# switch_2.net
KiCad netlist of a schematic drawn in Altium Designer
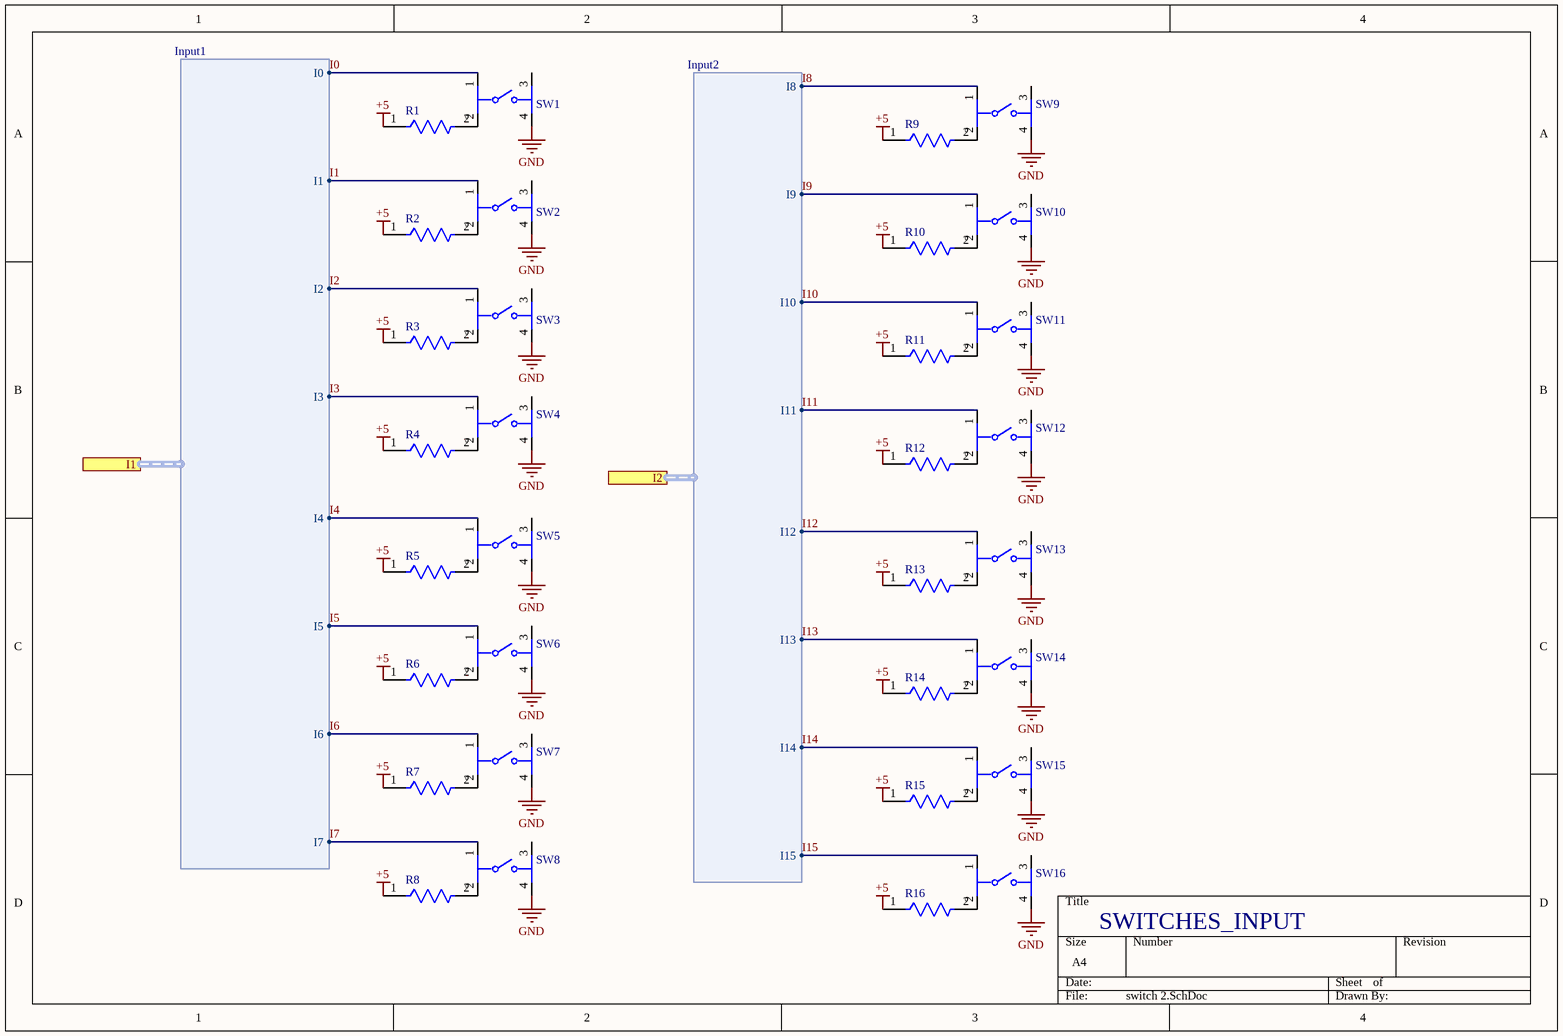
[diagram p0: switch 2.SchDoc]

(export (version "E")
  (design (tool "Eeschema 10.0.6"))
  (components
    (comp (ref "R1")
      (value "MRS25000C1001FCT00")
      (footprint "FP-MRS25-MFG")
      (description "RES 1K OHM 0.6W 1% AXIAL")
      (fields (field (name "TOLERANCE") "1%"))
      (libsource (lib "Altium Content Vault") (part "1029c3af85768c4190bb7ad29bc67b5"))
    )
    (comp (ref "R2")
      (value "MRS25000C1001FCT00")
      (footprint "FP-MRS25-MFG")
      (description "RES 1K OHM 0.6W 1% AXIAL")
      (fields (field (name "TOLERANCE") "1%"))
      (libsource (lib "Altium Content Vault") (part "1029c3af85768c4190bb7ad29bc67b5"))
    )
    (comp (ref "R3")
      (value "MRS25000C1001FCT00")
      (footprint "FP-MRS25-MFG")
      (description "RES 1K OHM 0.6W 1% AXIAL")
      (fields (field (name "TOLERANCE") "1%"))
      (libsource (lib "Altium Content Vault") (part "1029c3af85768c4190bb7ad29bc67b5"))
    )
    (comp (ref "R4")
      (value "MRS25000C1001FCT00")
      (footprint "FP-MRS25-MFG")
      (description "RES 1K OHM 0.6W 1% AXIAL")
      (fields (field (name "TOLERANCE") "1%"))
      (libsource (lib "Altium Content Vault") (part "1029c3af85768c4190bb7ad29bc67b5"))
    )
    (comp (ref "R5")
      (value "MRS25000C1001FCT00")
      (footprint "FP-MRS25-MFG")
      (description "RES 1K OHM 0.6W 1% AXIAL")
      (fields (field (name "TOLERANCE") "1%"))
      (libsource (lib "Altium Content Vault") (part "1029c3af85768c4190bb7ad29bc67b5"))
    )
    (comp (ref "R6")
      (value "MRS25000C1001FCT00")
      (footprint "FP-MRS25-MFG")
      (description "RES 1K OHM 0.6W 1% AXIAL")
      (fields (field (name "TOLERANCE") "1%"))
      (libsource (lib "Altium Content Vault") (part "1029c3af85768c4190bb7ad29bc67b5"))
    )
    (comp (ref "R7")
      (value "MRS25000C1001FCT00")
      (footprint "FP-MRS25-MFG")
      (description "RES 1K OHM 0.6W 1% AXIAL")
      (fields (field (name "TOLERANCE") "1%"))
      (libsource (lib "Altium Content Vault") (part "1029c3af85768c4190bb7ad29bc67b5"))
    )
    (comp (ref "R8")
      (value "MRS25000C1001FCT00")
      (footprint "FP-MRS25-MFG")
      (description "RES 1K OHM 0.6W 1% AXIAL")
      (fields (field (name "TOLERANCE") "1%"))
      (libsource (lib "Altium Content Vault") (part "1029c3af85768c4190bb7ad29bc67b5"))
    )
    (comp (ref "R9")
      (value "MRS25000C1001FCT00")
      (footprint "FP-MRS25-MFG")
      (description "RES 1K OHM 0.6W 1% AXIAL")
      (fields (field (name "TOLERANCE") "1%"))
      (libsource (lib "Altium Content Vault") (part "1029c3af85768c4190bb7ad29bc67b5"))
    )
    (comp (ref "R10")
      (value "MRS25000C1001FCT00")
      (footprint "FP-MRS25-MFG")
      (description "RES 1K OHM 0.6W 1% AXIAL")
      (fields (field (name "TOLERANCE") "1%"))
      (libsource (lib "Altium Content Vault") (part "1029c3af85768c4190bb7ad29bc67b5"))
    )
    (comp (ref "R11")
      (value "MRS25000C1001FCT00")
      (footprint "FP-MRS25-MFG")
      (description "RES 1K OHM 0.6W 1% AXIAL")
      (fields (field (name "TOLERANCE") "1%"))
      (libsource (lib "Altium Content Vault") (part "1029c3af85768c4190bb7ad29bc67b5"))
    )
    (comp (ref "R12")
      (value "MRS25000C1001FCT00")
      (footprint "FP-MRS25-MFG")
      (description "RES 1K OHM 0.6W 1% AXIAL")
      (fields (field (name "TOLERANCE") "1%"))
      (libsource (lib "Altium Content Vault") (part "1029c3af85768c4190bb7ad29bc67b5"))
    )
    (comp (ref "R13")
      (value "MRS25000C1001FCT00")
      (footprint "FP-MRS25-MFG")
      (description "RES 1K OHM 0.6W 1% AXIAL")
      (fields (field (name "TOLERANCE") "1%"))
      (libsource (lib "Altium Content Vault") (part "1029c3af85768c4190bb7ad29bc67b5"))
    )
    (comp (ref "R14")
      (value "MRS25000C1001FCT00")
      (footprint "FP-MRS25-MFG")
      (description "RES 1K OHM 0.6W 1% AXIAL")
      (fields (field (name "TOLERANCE") "1%"))
      (libsource (lib "Altium Content Vault") (part "1029c3af85768c4190bb7ad29bc67b5"))
    )
    (comp (ref "R15")
      (value "MRS25000C1001FCT00")
      (footprint "FP-MRS25-MFG")
      (description "RES 1K OHM 0.6W 1% AXIAL")
      (fields (field (name "TOLERANCE") "1%"))
      (libsource (lib "Altium Content Vault") (part "1029c3af85768c4190bb7ad29bc67b5"))
    )
    (comp (ref "R16")
      (value "MRS25000C1001FCT00")
      (footprint "FP-MRS25-MFG")
      (description "RES 1K OHM 0.6W 1% AXIAL")
      (fields (field (name "TOLERANCE") "1%"))
      (libsource (lib "Altium Content Vault") (part "1029c3af85768c4190bb7ad29bc67b5"))
    )
    (comp (ref "SW1")
      (value "1-1825910-5")
      (footprint "FP-1-1825910-5-MFG")
      (description "SWITCH TACTILE SPST-NO 0.05A 24V")
      (libsource (lib "Altium Content Vault") (part "b8895f3f4cefb76e1819d2863dba89b"))
    )
    (comp (ref "SW2")
      (value "1-1825910-5")
      (footprint "FP-1-1825910-5-MFG")
      (description "SWITCH TACTILE SPST-NO 0.05A 24V")
      (libsource (lib "Altium Content Vault") (part "b8895f3f4cefb76e1819d2863dba89b"))
    )
    (comp (ref "SW3")
      (value "1-1825910-5")
      (footprint "FP-1-1825910-5-MFG")
      (description "SWITCH TACTILE SPST-NO 0.05A 24V")
      (libsource (lib "Altium Content Vault") (part "b8895f3f4cefb76e1819d2863dba89b"))
    )
    (comp (ref "SW4")
      (value "1-1825910-5")
      (footprint "FP-1-1825910-5-MFG")
      (description "SWITCH TACTILE SPST-NO 0.05A 24V")
      (libsource (lib "Altium Content Vault") (part "b8895f3f4cefb76e1819d2863dba89b"))
    )
    (comp (ref "SW5")
      (value "1-1825910-5")
      (footprint "FP-1-1825910-5-MFG")
      (description "SWITCH TACTILE SPST-NO 0.05A 24V")
      (libsource (lib "Altium Content Vault") (part "b8895f3f4cefb76e1819d2863dba89b"))
    )
    (comp (ref "SW6")
      (value "1-1825910-5")
      (footprint "FP-1-1825910-5-MFG")
      (description "SWITCH TACTILE SPST-NO 0.05A 24V")
      (libsource (lib "Altium Content Vault") (part "b8895f3f4cefb76e1819d2863dba89b"))
    )
    (comp (ref "SW7")
      (value "1-1825910-5")
      (footprint "FP-1-1825910-5-MFG")
      (description "SWITCH TACTILE SPST-NO 0.05A 24V")
      (libsource (lib "Altium Content Vault") (part "b8895f3f4cefb76e1819d2863dba89b"))
    )
    (comp (ref "SW8")
      (value "1-1825910-5")
      (footprint "FP-1-1825910-5-MFG")
      (description "SWITCH TACTILE SPST-NO 0.05A 24V")
      (libsource (lib "Altium Content Vault") (part "b8895f3f4cefb76e1819d2863dba89b"))
    )
    (comp (ref "SW9")
      (value "1-1825910-5")
      (footprint "FP-1-1825910-5-MFG")
      (description "SWITCH TACTILE SPST-NO 0.05A 24V")
      (libsource (lib "Altium Content Vault") (part "b8895f3f4cefb76e1819d2863dba89b"))
    )
    (comp (ref "SW10")
      (value "1-1825910-5")
      (footprint "FP-1-1825910-5-MFG")
      (description "SWITCH TACTILE SPST-NO 0.05A 24V")
      (libsource (lib "Altium Content Vault") (part "b8895f3f4cefb76e1819d2863dba89b"))
    )
    (comp (ref "SW11")
      (value "1-1825910-5")
      (footprint "FP-1-1825910-5-MFG")
      (description "SWITCH TACTILE SPST-NO 0.05A 24V")
      (libsource (lib "Altium Content Vault") (part "b8895f3f4cefb76e1819d2863dba89b"))
    )
    (comp (ref "SW12")
      (value "1-1825910-5")
      (footprint "FP-1-1825910-5-MFG")
      (description "SWITCH TACTILE SPST-NO 0.05A 24V")
      (libsource (lib "Altium Content Vault") (part "b8895f3f4cefb76e1819d2863dba89b"))
    )
    (comp (ref "SW13")
      (value "1-1825910-5")
      (footprint "FP-1-1825910-5-MFG")
      (description "SWITCH TACTILE SPST-NO 0.05A 24V")
      (libsource (lib "Altium Content Vault") (part "b8895f3f4cefb76e1819d2863dba89b"))
    )
    (comp (ref "SW14")
      (value "1-1825910-5")
      (footprint "FP-1-1825910-5-MFG")
      (description "SWITCH TACTILE SPST-NO 0.05A 24V")
      (libsource (lib "Altium Content Vault") (part "b8895f3f4cefb76e1819d2863dba89b"))
    )
    (comp (ref "SW15")
      (value "1-1825910-5")
      (footprint "FP-1-1825910-5-MFG")
      (description "SWITCH TACTILE SPST-NO 0.05A 24V")
      (libsource (lib "Altium Content Vault") (part "b8895f3f4cefb76e1819d2863dba89b"))
    )
    (comp (ref "SW16")
      (value "1-1825910-5")
      (footprint "FP-1-1825910-5-MFG")
      (description "SWITCH TACTILE SPST-NO 0.05A 24V")
      (libsource (lib "Altium Content Vault") (part "b8895f3f4cefb76e1819d2863dba89b"))
    )
  )
  (nets
    (net (code "3") (name "+5") (class "Default")
      (node (ref "R1") (pin "1") (pinfunction "1_1") (pintype "passive"))
      (node (ref "R10") (pin "1") (pinfunction "1_1") (pintype "passive"))
      (node (ref "R11") (pin "1") (pinfunction "1_1") (pintype "passive"))
      (node (ref "R12") (pin "1") (pinfunction "1_1") (pintype "passive"))
      (node (ref "R13") (pin "1") (pinfunction "1_1") (pintype "passive"))
      (node (ref "R14") (pin "1") (pinfunction "1_1") (pintype "passive"))
      (node (ref "R15") (pin "1") (pinfunction "1_1") (pintype "passive"))
      (node (ref "R16") (pin "1") (pinfunction "1_1") (pintype "passive"))
      (node (ref "R2") (pin "1") (pinfunction "1_1") (pintype "passive"))
      (node (ref "R3") (pin "1") (pinfunction "1_1") (pintype "passive"))
      (node (ref "R4") (pin "1") (pinfunction "1_1") (pintype "passive"))
      (node (ref "R5") (pin "1") (pinfunction "1_1") (pintype "passive"))
      (node (ref "R6") (pin "1") (pinfunction "1_1") (pintype "passive"))
      (node (ref "R7") (pin "1") (pinfunction "1_1") (pintype "passive"))
      (node (ref "R8") (pin "1") (pinfunction "1_1") (pintype "passive"))
      (node (ref "R9") (pin "1") (pinfunction "1_1") (pintype "passive"))
    )
    (net (code "4") (name "/I0") (class "Default")
      (node (ref "SW1") (pin "1") (pinfunction "1_1") (pintype "passive"))
    )
    (net (code "5") (name "/I1") (class "Default")
      (node (ref "SW2") (pin "1") (pinfunction "1_1") (pintype "passive"))
    )
    (net (code "6") (name "/I2") (class "Default")
      (node (ref "SW3") (pin "1") (pinfunction "1_1") (pintype "passive"))
    )
    (net (code "7") (name "/I3") (class "Default")
      (node (ref "SW4") (pin "1") (pinfunction "1_1") (pintype "passive"))
    )
    (net (code "8") (name "/I4") (class "Default")
      (node (ref "SW5") (pin "1") (pinfunction "1_1") (pintype "passive"))
    )
    (net (code "9") (name "/I5") (class "Default")
      (node (ref "SW6") (pin "1") (pinfunction "1_1") (pintype "passive"))
    )
    (net (code "10") (name "/I6") (class "Default")
      (node (ref "SW7") (pin "1") (pinfunction "1_1") (pintype "passive"))
    )
    (net (code "11") (name "/I7") (class "Default")
      (node (ref "SW8") (pin "1") (pinfunction "1_1") (pintype "passive"))
    )
    (net (code "12") (name "/I8") (class "Default")
      (node (ref "SW9") (pin "1") (pinfunction "1_1") (pintype "passive"))
    )
    (net (code "13") (name "/I9") (class "Default")
      (node (ref "SW10") (pin "1") (pinfunction "1_1") (pintype "passive"))
    )
    (net (code "14") (name "/I10") (class "Default")
      (node (ref "SW11") (pin "1") (pinfunction "1_1") (pintype "passive"))
    )
    (net (code "15") (name "/I11") (class "Default")
      (node (ref "SW12") (pin "1") (pinfunction "1_1") (pintype "passive"))
    )
    (net (code "16") (name "/I12") (class "Default")
      (node (ref "SW13") (pin "1") (pinfunction "1_1") (pintype "passive"))
    )
    (net (code "17") (name "/I13") (class "Default")
      (node (ref "SW14") (pin "1") (pinfunction "1_1") (pintype "passive"))
    )
    (net (code "18") (name "/I14") (class "Default")
      (node (ref "SW15") (pin "1") (pinfunction "1_1") (pintype "passive"))
    )
    (net (code "19") (name "/I15") (class "Default")
      (node (ref "SW16") (pin "1") (pinfunction "1_1") (pintype "passive"))
    )
    (net (code "22") (name "GND") (class "Default")
      (node (ref "SW1") (pin "4") (pinfunction "4_4") (pintype "passive"))
      (node (ref "SW10") (pin "4") (pinfunction "4_4") (pintype "passive"))
      (node (ref "SW11") (pin "4") (pinfunction "4_4") (pintype "passive"))
      (node (ref "SW12") (pin "4") (pinfunction "4_4") (pintype "passive"))
      (node (ref "SW13") (pin "4") (pinfunction "4_4") (pintype "passive"))
      (node (ref "SW14") (pin "4") (pinfunction "4_4") (pintype "passive"))
      (node (ref "SW15") (pin "4") (pinfunction "4_4") (pintype "passive"))
      (node (ref "SW16") (pin "4") (pinfunction "4_4") (pintype "passive"))
      (node (ref "SW2") (pin "4") (pinfunction "4_4") (pintype "passive"))
      (node (ref "SW3") (pin "4") (pinfunction "4_4") (pintype "passive"))
      (node (ref "SW4") (pin "4") (pinfunction "4_4") (pintype "passive"))
      (node (ref "SW5") (pin "4") (pinfunction "4_4") (pintype "passive"))
      (node (ref "SW6") (pin "4") (pinfunction "4_4") (pintype "passive"))
      (node (ref "SW7") (pin "4") (pinfunction "4_4") (pintype "passive"))
      (node (ref "SW8") (pin "4") (pinfunction "4_4") (pintype "passive"))
      (node (ref "SW9") (pin "4") (pinfunction "4_4") (pintype "passive"))
    )
    (net (code "23") (name "Net-(R1-Pad2)") (class "Default")
      (node (ref "R1") (pin "2") (pinfunction "2_2") (pintype "passive"))
      (node (ref "SW1") (pin "2") (pinfunction "2_2") (pintype "passive"))
    )
    (net (code "24") (name "Net-(R2-Pad2)") (class "Default")
      (node (ref "R2") (pin "2") (pinfunction "2_2") (pintype "passive"))
      (node (ref "SW2") (pin "2") (pinfunction "2_2") (pintype "passive"))
    )
    (net (code "25") (name "Net-(R3-Pad2)") (class "Default")
      (node (ref "R3") (pin "2") (pinfunction "2_2") (pintype "passive"))
      (node (ref "SW3") (pin "2") (pinfunction "2_2") (pintype "passive"))
    )
    (net (code "26") (name "Net-(R4-Pad2)") (class "Default")
      (node (ref "R4") (pin "2") (pinfunction "2_2") (pintype "passive"))
      (node (ref "SW4") (pin "2") (pinfunction "2_2") (pintype "passive"))
    )
    (net (code "27") (name "Net-(R5-Pad2)") (class "Default")
      (node (ref "R5") (pin "2") (pinfunction "2_2") (pintype "passive"))
      (node (ref "SW5") (pin "2") (pinfunction "2_2") (pintype "passive"))
    )
    (net (code "28") (name "Net-(R6-Pad2)") (class "Default")
      (node (ref "R6") (pin "2") (pinfunction "2_2") (pintype "passive"))
      (node (ref "SW6") (pin "2") (pinfunction "2_2") (pintype "passive"))
    )
    (net (code "29") (name "Net-(R7-Pad2)") (class "Default")
      (node (ref "R7") (pin "2") (pinfunction "2_2") (pintype "passive"))
      (node (ref "SW7") (pin "2") (pinfunction "2_2") (pintype "passive"))
    )
    (net (code "30") (name "Net-(R8-Pad2)") (class "Default")
      (node (ref "R8") (pin "2") (pinfunction "2_2") (pintype "passive"))
      (node (ref "SW8") (pin "2") (pinfunction "2_2") (pintype "passive"))
    )
    (net (code "31") (name "Net-(R9-Pad2)") (class "Default")
      (node (ref "R9") (pin "2") (pinfunction "2_2") (pintype "passive"))
      (node (ref "SW9") (pin "2") (pinfunction "2_2") (pintype "passive"))
    )
    (net (code "32") (name "Net-(R10-Pad2)") (class "Default")
      (node (ref "R10") (pin "2") (pinfunction "2_2") (pintype "passive"))
      (node (ref "SW10") (pin "2") (pinfunction "2_2") (pintype "passive"))
    )
    (net (code "33") (name "Net-(R11-Pad2)") (class "Default")
      (node (ref "R11") (pin "2") (pinfunction "2_2") (pintype "passive"))
      (node (ref "SW11") (pin "2") (pinfunction "2_2") (pintype "passive"))
    )
    (net (code "34") (name "Net-(R12-Pad2)") (class "Default")
      (node (ref "R12") (pin "2") (pinfunction "2_2") (pintype "passive"))
      (node (ref "SW12") (pin "2") (pinfunction "2_2") (pintype "passive"))
    )
    (net (code "35") (name "Net-(R13-Pad2)") (class "Default")
      (node (ref "R13") (pin "2") (pinfunction "2_2") (pintype "passive"))
      (node (ref "SW13") (pin "2") (pinfunction "2_2") (pintype "passive"))
    )
    (net (code "36") (name "Net-(R14-Pad2)") (class "Default")
      (node (ref "R14") (pin "2") (pinfunction "2_2") (pintype "passive"))
      (node (ref "SW14") (pin "2") (pinfunction "2_2") (pintype "passive"))
    )
    (net (code "37") (name "Net-(R15-Pad2)") (class "Default")
      (node (ref "R15") (pin "2") (pinfunction "2_2") (pintype "passive"))
      (node (ref "SW15") (pin "2") (pinfunction "2_2") (pintype "passive"))
    )
    (net (code "38") (name "Net-(R16-Pad2)") (class "Default")
      (node (ref "R16") (pin "2") (pinfunction "2_2") (pintype "passive"))
      (node (ref "SW16") (pin "2") (pinfunction "2_2") (pintype "passive"))
    )
    (net (code "39") (name "unconnected-(SW1-Pad3)") (class "Default")
      (node (ref "SW1") (pin "3") (pinfunction "3_3") (pintype "passive"))
    )
    (net (code "40") (name "unconnected-(SW2-Pad3)") (class "Default")
      (node (ref "SW2") (pin "3") (pinfunction "3_3") (pintype "passive"))
    )
    (net (code "41") (name "unconnected-(SW3-Pad3)") (class "Default")
      (node (ref "SW3") (pin "3") (pinfunction "3_3") (pintype "passive"))
    )
    (net (code "42") (name "unconnected-(SW4-Pad3)") (class "Default")
      (node (ref "SW4") (pin "3") (pinfunction "3_3") (pintype "passive"))
    )
    (net (code "43") (name "unconnected-(SW5-Pad3)") (class "Default")
      (node (ref "SW5") (pin "3") (pinfunction "3_3") (pintype "passive"))
    )
    (net (code "44") (name "unconnected-(SW6-Pad3)") (class "Default")
      (node (ref "SW6") (pin "3") (pinfunction "3_3") (pintype "passive"))
    )
    (net (code "45") (name "unconnected-(SW7-Pad3)") (class "Default")
      (node (ref "SW7") (pin "3") (pinfunction "3_3") (pintype "passive"))
    )
    (net (code "46") (name "unconnected-(SW8-Pad3)") (class "Default")
      (node (ref "SW8") (pin "3") (pinfunction "3_3") (pintype "passive"))
    )
    (net (code "47") (name "unconnected-(SW9-Pad3)") (class "Default")
      (node (ref "SW9") (pin "3") (pinfunction "3_3") (pintype "passive"))
    )
    (net (code "48") (name "unconnected-(SW10-Pad3)") (class "Default")
      (node (ref "SW10") (pin "3") (pinfunction "3_3") (pintype "passive"))
    )
    (net (code "49") (name "unconnected-(SW11-Pad3)") (class "Default")
      (node (ref "SW11") (pin "3") (pinfunction "3_3") (pintype "passive"))
    )
    (net (code "50") (name "unconnected-(SW12-Pad3)") (class "Default")
      (node (ref "SW12") (pin "3") (pinfunction "3_3") (pintype "passive"))
    )
    (net (code "51") (name "unconnected-(SW13-Pad3)") (class "Default")
      (node (ref "SW13") (pin "3") (pinfunction "3_3") (pintype "passive"))
    )
    (net (code "52") (name "unconnected-(SW14-Pad3)") (class "Default")
      (node (ref "SW14") (pin "3") (pinfunction "3_3") (pintype "passive"))
    )
    (net (code "53") (name "unconnected-(SW15-Pad3)") (class "Default")
      (node (ref "SW15") (pin "3") (pinfunction "3_3") (pintype "passive"))
    )
    (net (code "54") (name "unconnected-(SW16-Pad3)") (class "Default")
      (node (ref "SW16") (pin "3") (pinfunction "3_3") (pintype "passive"))
    )
  )
)
